# v002.net
KiCad netlist of a schematic drawn in EAGLE
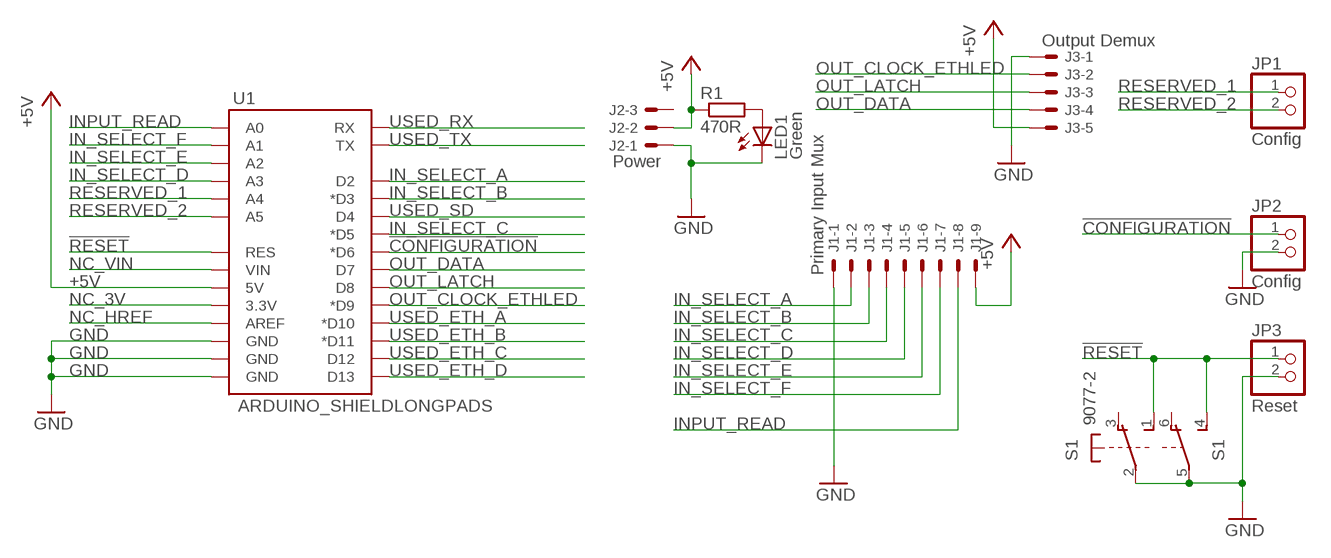
[diagram p0: schematic, sheet 1]

(export (version "E")
  (design (tool "Eeschema 10.0.6"))
  (components
    (comp (ref "J1")
      (value "Primary Input Mux")
      (footprint "eagle-import:6410-09")
      (libsource (lib "eagle-import") (part "22-?-0927-2091"))
    )
    (comp (ref "J2")
      (value "Power")
      (footprint "eagle-import:6410-03")
      (libsource (lib "eagle-import") (part "22-?-0327-2031"))
    )
    (comp (ref "J3")
      (value "Output Demux")
      (footprint "eagle-import:6410-05")
      (libsource (lib "eagle-import") (part "22-?-0527-2051"))
    )
    (comp (ref "JP1")
      (value "Config")
      (footprint "eagle-import:1X02")
      (libsource (lib "eagle-import") (part "PINHD-1X2"))
    )
    (comp (ref "JP2")
      (value "Config")
      (footprint "eagle-import:1X02")
      (libsource (lib "eagle-import") (part "PINHD-1X2"))
    )
    (comp (ref "JP3")
      (value "Reset")
      (footprint "eagle-import:1X02")
      (libsource (lib "eagle-import") (part "PINHD-1X2"))
    )
    (comp (ref "LED1")
      (value "Green")
      (footprint "eagle-import:LED3MM")
      (libsource (lib "eagle-import") (part "LED3MM"))
    )
    (comp (ref "R1")
      (value "470R")
      (footprint "eagle-import:0204_7")
      (libsource (lib "eagle-import") (part "R-EU_0204/7"))
    )
    (comp (ref "S1")
      (value "9077-2")
      (footprint "eagle-import:9077-2")
      (libsource (lib "eagle-import") (part "9077-2"))
    )
    (comp (ref "U1")
      (value "ARDUINO_SHIELDLONGPADS")
      (footprint "eagle-import:DUEMILANOVE_SHIELD_LONGPADS")
      (libsource (lib "eagle-import") (part "ARDUINO_SHIELDLONGPADS"))
    )
  )
  (nets
    (net (code "1") (name "+5V") (class "Default")
      (node (ref "J1") (pin "9") (pinfunction "S_9") (pintype "passive"))
      (node (ref "J2") (pin "2") (pinfunction "S_2") (pintype "passive"))
      (node (ref "J3") (pin "5") (pinfunction "S_5") (pintype "passive"))
      (node (ref "R1") (pin "1") (pinfunction "1_1") (pintype "passive"))
      (node (ref "U1") (pin "5V") (pinfunction "5V_5V") (pintype "bidirectional"))
    )
    (net (code "2") (name "/INPUT_READ") (class "Default")
      (node (ref "J1") (pin "8") (pinfunction "S_8") (pintype "passive"))
      (node (ref "U1") (pin "A0") (pinfunction "A0_A0") (pintype "bidirectional"))
    )
    (net (code "3") (name "/IN_SELECT_A") (class "Default")
      (node (ref "J1") (pin "2") (pinfunction "S_2") (pintype "passive"))
      (node (ref "U1") (pin "D2") (pinfunction "D2_D2") (pintype "bidirectional"))
    )
    (net (code "4") (name "/IN_SELECT_B") (class "Default")
      (node (ref "J1") (pin "3") (pinfunction "S_3") (pintype "passive"))
      (node (ref "U1") (pin "D3") (pinfunction "*D3_D3") (pintype "bidirectional"))
    )
    (net (code "5") (name "/IN_SELECT_C") (class "Default")
      (node (ref "J1") (pin "4") (pinfunction "S_4") (pintype "passive"))
      (node (ref "U1") (pin "D5") (pinfunction "*D5_D5") (pintype "bidirectional"))
    )
    (net (code "6") (name "/IN_SELECT_D") (class "Default")
      (node (ref "J1") (pin "5") (pinfunction "S_5") (pintype "passive"))
      (node (ref "U1") (pin "A3") (pinfunction "A3_A3") (pintype "bidirectional"))
    )
    (net (code "7") (name "/IN_SELECT_E") (class "Default")
      (node (ref "J1") (pin "6") (pinfunction "S_6") (pintype "passive"))
      (node (ref "U1") (pin "A2") (pinfunction "A2_A2") (pintype "bidirectional"))
    )
    (net (code "8") (name "/IN_SELECT_F") (class "Default")
      (node (ref "J1") (pin "7") (pinfunction "S_7") (pintype "passive"))
      (node (ref "U1") (pin "A1") (pinfunction "A1_A1") (pintype "bidirectional"))
    )
    (net (code "9") (name "/NC_3V") (class "Default")
      (node (ref "U1") (pin "3.3V") (pinfunction "3.3V_3.3V") (pintype "bidirectional"))
    )
    (net (code "10") (name "/NC_HREF") (class "Default")
      (node (ref "U1") (pin "AREF") (pinfunction "AREF_AREF") (pintype "bidirectional"))
    )
    (net (code "11") (name "/NC_VIN") (class "Default")
      (node (ref "U1") (pin "VIN") (pinfunction "VIN_VIN") (pintype "bidirectional"))
    )
    (net (code "12") (name "/OUT_CLOCK_ETHLED") (class "Default")
      (node (ref "J3") (pin "2") (pinfunction "S_2") (pintype "passive"))
      (node (ref "U1") (pin "D9") (pinfunction "*D9_D9") (pintype "bidirectional"))
    )
    (net (code "13") (name "/OUT_DATA") (class "Default")
      (node (ref "J3") (pin "4") (pinfunction "S_4") (pintype "passive"))
      (node (ref "U1") (pin "D7") (pinfunction "D7_D7") (pintype "bidirectional"))
    )
    (net (code "14") (name "/OUT_LATCH") (class "Default")
      (node (ref "J3") (pin "3") (pinfunction "S_3") (pintype "passive"))
      (node (ref "U1") (pin "D8") (pinfunction "D8_D8") (pintype "bidirectional"))
    )
    (net (code "15") (name "/RESERVED_1") (class "Default")
      (node (ref "JP1") (pin "1") (pinfunction "1_1") (pintype "passive"))
      (node (ref "U1") (pin "A4") (pinfunction "A4_A4") (pintype "bidirectional"))
    )
    (net (code "16") (name "/RESERVED_2") (class "Default")
      (node (ref "JP1") (pin "2") (pinfunction "2_2") (pintype "passive"))
      (node (ref "U1") (pin "A5") (pinfunction "A5_A5") (pintype "bidirectional"))
    )
    (net (code "17") (name "/USED_ETH_A") (class "Default")
      (node (ref "U1") (pin "D10") (pinfunction "*D10_D10") (pintype "bidirectional"))
    )
    (net (code "18") (name "/USED_ETH_B") (class "Default")
      (node (ref "U1") (pin "D11") (pinfunction "*D11_D11") (pintype "bidirectional"))
    )
    (net (code "19") (name "/USED_ETH_C") (class "Default")
      (node (ref "U1") (pin "D12") (pinfunction "D12_D12") (pintype "bidirectional"))
    )
    (net (code "20") (name "/USED_ETH_D") (class "Default")
      (node (ref "U1") (pin "D13") (pinfunction "D13_D13") (pintype "bidirectional"))
    )
    (net (code "21") (name "/USED_RX") (class "Default")
      (node (ref "U1") (pin "RX") (pinfunction "RX_RX") (pintype "bidirectional"))
    )
    (net (code "22") (name "/USED_SD") (class "Default")
      (node (ref "U1") (pin "D4") (pinfunction "D4_D4") (pintype "bidirectional"))
    )
    (net (code "23") (name "/USED_TX") (class "Default")
      (node (ref "U1") (pin "TX") (pinfunction "TX_TX") (pintype "bidirectional"))
    )
    (net (code "24") (name "/~{CONFIGURATION}") (class "Default")
      (node (ref "JP2") (pin "1") (pinfunction "1_1") (pintype "passive"))
      (node (ref "U1") (pin "D6") (pinfunction "*D6_D6") (pintype "bidirectional"))
    )
    (net (code "25") (name "/~{RESET}") (class "Default")
      (node (ref "JP3") (pin "1") (pinfunction "1_1") (pintype "passive"))
      (node (ref "S1") (pin "1") (pinfunction "S_1") (pintype "passive"))
      (node (ref "S1") (pin "4") (pinfunction "S_4") (pintype "passive"))
      (node (ref "U1") (pin "RES") (pinfunction "RES_RES") (pintype "bidirectional"))
    )
    (net (code "26") (name "GND") (class "Default")
      (node (ref "J1") (pin "1") (pinfunction "S_1") (pintype "passive"))
      (node (ref "J2") (pin "1") (pinfunction "S_1") (pintype "passive"))
      (node (ref "J3") (pin "1") (pinfunction "S_1") (pintype "passive"))
      (node (ref "JP2") (pin "2") (pinfunction "2_2") (pintype "passive"))
      (node (ref "JP3") (pin "2") (pinfunction "2_2") (pintype "passive"))
      (node (ref "LED1") (pin "K") (pinfunction "C_K") (pintype "passive"))
      (node (ref "S1") (pin "2") (pinfunction "P_2") (pintype "passive"))
      (node (ref "S1") (pin "5") (pinfunction "P_5") (pintype "passive"))
      (node (ref "U1") (pin "GND@0") (pinfunction "GND_GND@0") (pintype "bidirectional"))
      (node (ref "U1") (pin "GND@1") (pinfunction "GND_GND@1") (pintype "bidirectional"))
      (node (ref "U1") (pin "GND@2") (pinfunction "GND_GND@2") (pintype "bidirectional"))
    )
    (net (code "27") (name "Net-(LED1-PadA)") (class "Default")
      (node (ref "LED1") (pin "A") (pinfunction "A_A") (pintype "passive"))
      (node (ref "R1") (pin "2") (pinfunction "2_2") (pintype "passive"))
    )
    (net (code "28") (name "unconnected-(J2C-S-Pad3)") (class "Default")
      (node (ref "J2") (pin "3") (pinfunction "S_3") (pintype "passive"))
    )
    (net (code "29") (name "unconnected-(S1A-O-Pad3)") (class "Default")
      (node (ref "S1") (pin "3") (pinfunction "O_3") (pintype "passive"))
    )
    (net (code "30") (name "unconnected-(S1B-O-Pad6)") (class "Default")
      (node (ref "S1") (pin "6") (pinfunction "O_6") (pintype "passive"))
    )
  )
)
